# mixer-MAC-24.net
KiCad netlist of a schematic drawn in EAGLE
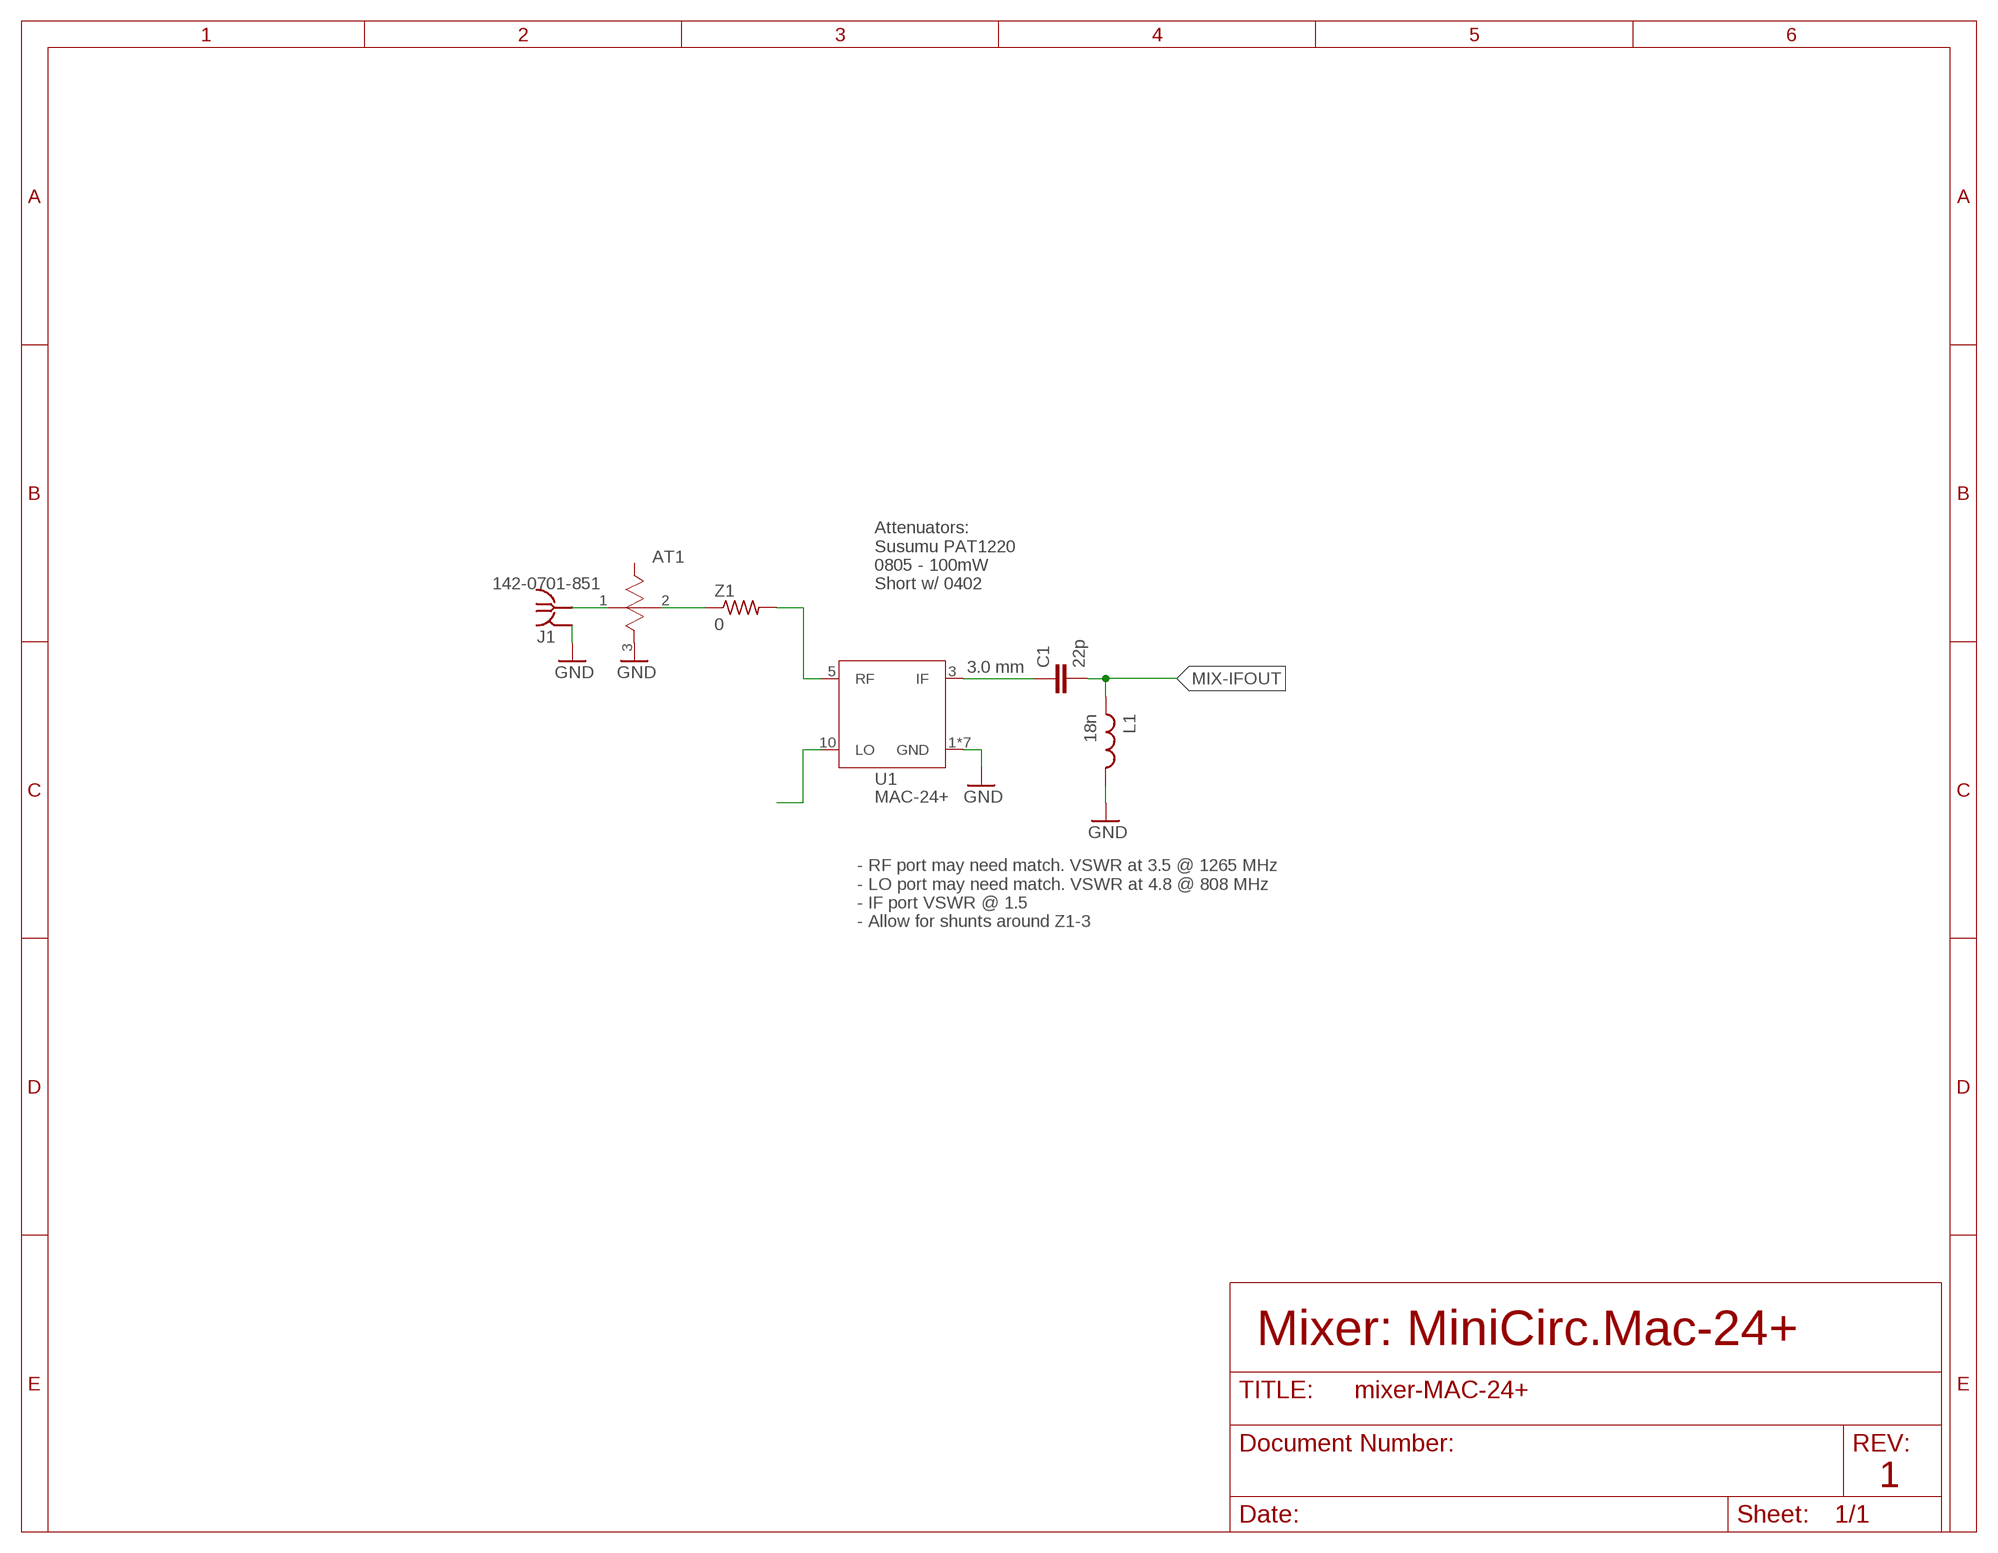
[diagram p0: schematic, sheet 1]

(export (version "E")
  (design (tool "Eeschema 10.0.6"))
  (components
    (comp (ref "AT1")
      (value "PAT1220")
      (footprint "eagle-import:0805")
      (libsource (lib "eagle-import") (part "PAT1220"))
    )
    (comp (ref "C1")
      (value "22p")
      (footprint "eagle-import:.0402-B-NOSILK")
      (libsource (lib "eagle-import") (part "C-EU0402-B-NOSILK"))
    )
    (comp (ref "J1")
      (value "142-0701-851")
      (footprint "eagle-import:142-0701-851")
      (libsource (lib "eagle-import") (part "142-0701-851"))
    )
    (comp (ref "L1")
      (value "18n")
      (footprint "eagle-import:.0402-B-NOSILK")
      (libsource (lib "eagle-import") (part "L-US0402-B-NOSILK"))
    )
    (comp (ref "U1")
      (value "MAC-24+")
      (footprint "eagle-import:MAC-24+")
      (libsource (lib "eagle-import") (part "MAC-24+"))
    )
    (comp (ref "Z1")
      (value "0")
      (footprint "eagle-import:.0402-C-NOSILK")
      (libsource (lib "eagle-import") (part "R-US_0402-C-NOSILK"))
    )
  )
  (nets
    (net (code "1") (name "GND") (class "Default")
      (node (ref "AT1") (pin "3") (pinfunction "GND_3") (pintype "power_in"))
      (node (ref "J1") (pin "GND1") (pinfunction "GND_GND1") (pintype "bidirectional"))
      (node (ref "J1") (pin "GND2") (pinfunction "GND_GND2") (pintype "bidirectional"))
      (node (ref "J1") (pin "GND3") (pinfunction "GND_GND3") (pintype "bidirectional"))
      (node (ref "J1") (pin "GND4") (pinfunction "GND_GND4") (pintype "bidirectional"))
      (node (ref "L1") (pin "2") (pinfunction "2_2") (pintype "passive"))
      (node (ref "U1") (pin "1") (pinfunction "GND_1") (pintype "power_in"))
      (node (ref "U1") (pin "2") (pinfunction "GND_2") (pintype "power_in"))
      (node (ref "U1") (pin "4") (pinfunction "GND_4") (pintype "power_in"))
      (node (ref "U1") (pin "6") (pinfunction "GND_6") (pintype "power_in"))
      (node (ref "U1") (pin "7") (pinfunction "GND_7") (pintype "power_in"))
      (node (ref "U1") (pin "8") (pinfunction "GND_8") (pintype "power_in"))
      (node (ref "U1") (pin "9") (pinfunction "GND_9") (pintype "power_in"))
    )
    (net (code "2") (name "MIX-IFOUT") (class "Default")
      (node (ref "C1") (pin "2") (pinfunction "2_2") (pintype "passive"))
      (node (ref "L1") (pin "1") (pinfunction "1_1") (pintype "passive"))
    )
    (net (code "3") (name "Net-(AT1-Pad2)") (class "Default")
      (node (ref "AT1") (pin "2") (pinfunction "2_2") (pintype "bidirectional"))
      (node (ref "Z1") (pin "1") (pinfunction "1_1") (pintype "passive"))
    )
    (net (code "4") (name "Net-(J1-RF)") (class "Default")
      (node (ref "AT1") (pin "1") (pinfunction "1_1") (pintype "bidirectional"))
      (node (ref "J1") (pin "RF1") (pinfunction "RF_RF1") (pintype "bidirectional"))
    )
    (net (code "5") (name "Net-(U1-IF)") (class "Default")
      (node (ref "C1") (pin "1") (pinfunction "1_1") (pintype "passive"))
      (node (ref "U1") (pin "3") (pinfunction "IF_3") (pintype "output"))
    )
    (net (code "6") (name "Net-(U1-RF)") (class "Default")
      (node (ref "U1") (pin "5") (pinfunction "RF_5") (pintype "input"))
      (node (ref "Z1") (pin "2") (pinfunction "2_2") (pintype "passive"))
    )
    (net (code "7") (name "unconnected-(U1-LO-Pad10)") (class "Default")
      (node (ref "U1") (pin "10") (pinfunction "LO_10") (pintype "input"))
    )
  )
)
